# USBSticker01-01.net
KiCad netlist of a schematic drawn in Altium Designer
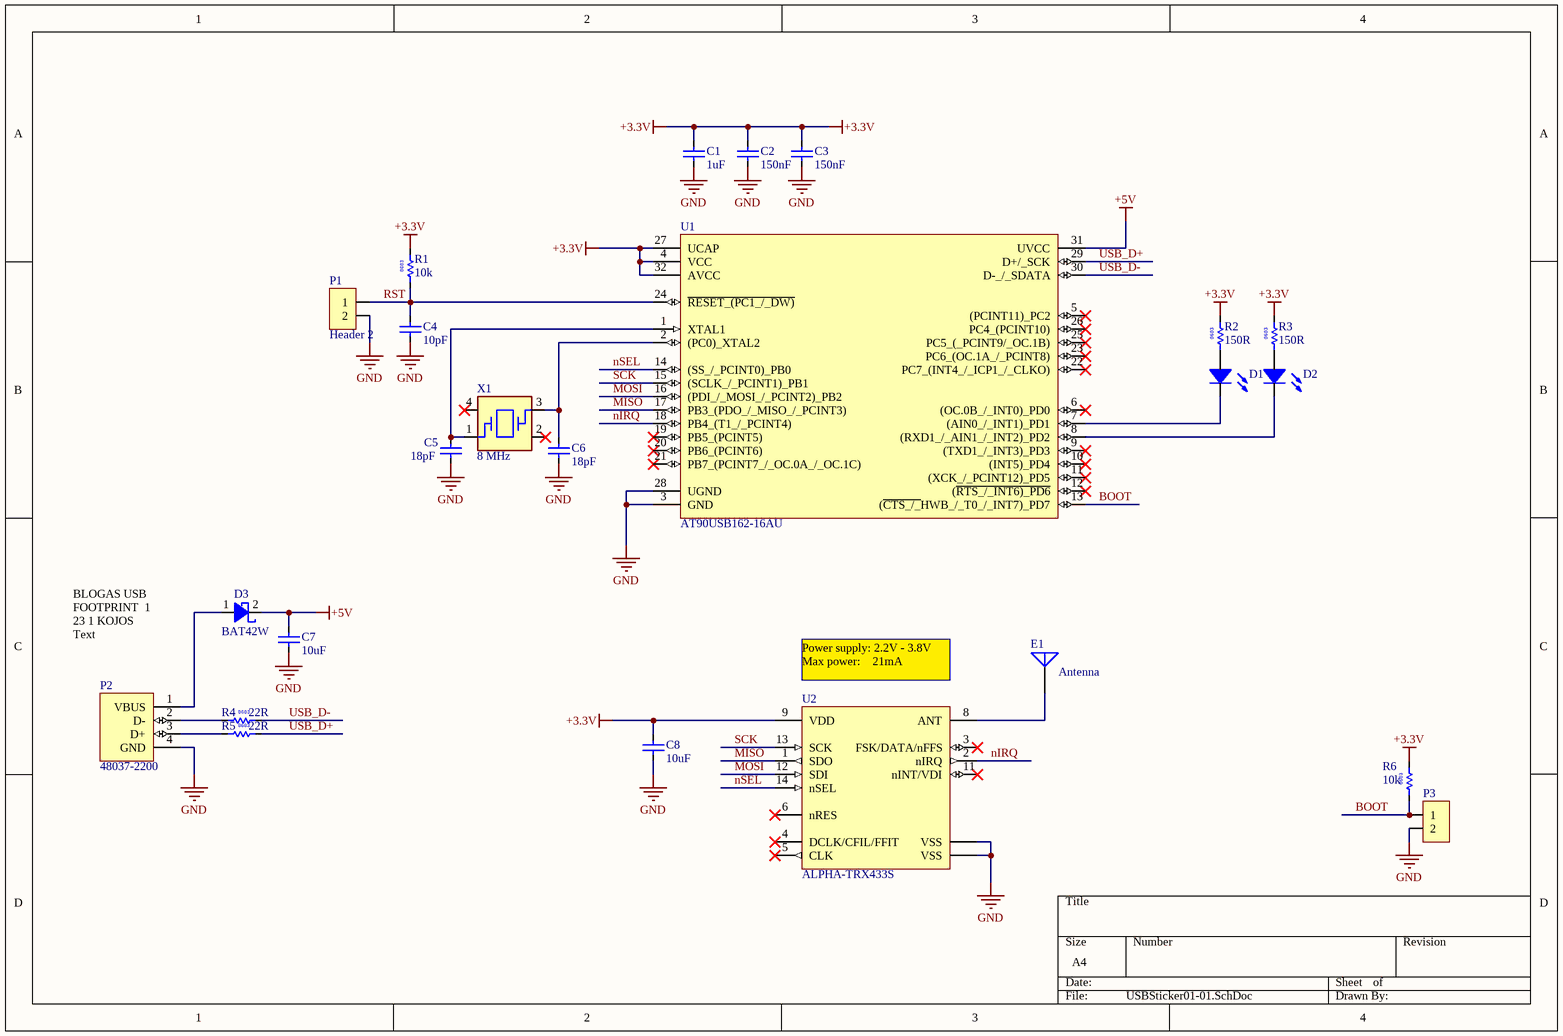
[diagram p0: USBSticker01-01.SchDoc]

(export (version "E")
  (design (tool "Eeschema 10.0.6"))
  (components
    (comp (ref "C1")
      (value "1uF")
      (footprint "CAPC1608N")
      (description "MLCC, 0603, X6S, 25V, 1uF")
      (fields (field (name "PART NUMBER") "C0000022") (field (name "VOLTAGE") "25"))
      (libsource (lib "KTU_DB") (part "C_SM"))
    )
    (comp (ref "C2")
      (value "150nF")
      (footprint "CAPC1608N")
      (description "MLCC, 150nF 16V -20+80% Y5V")
      (fields (field (name "PART NUMBER") "C0000001") (field (name "VOLTAGE") "16"))
      (libsource (lib "KTU_DB") (part "C_SM"))
    )
    (comp (ref "C3")
      (value "150nF")
      (footprint "CAPC1608N")
      (description "MLCC, 150nF 16V -20+80% Y5V")
      (fields (field (name "PART NUMBER") "C0000001") (field (name "VOLTAGE") "16"))
      (libsource (lib "KTU_DB") (part "C_SM"))
    )
    (comp (ref "C4")
      (value "10pF")
      (footprint "CAPC1608N")
      (description "MLCC, 0603, NP0, 50V, 10PF")
      (fields (field (name "PART NUMBER") "C0000042") (field (name "VOLTAGE") "100"))
      (libsource (lib "KTU_DB") (part "C_SM"))
    )
    (comp (ref "C5")
      (value "18pF")
      (footprint "CAPC2012N")
      (description "MLCC, 0805, NPO, 50V, 18pF")
      (fields (field (name "PART NUMBER") "C0000048") (field (name "VOLTAGE") "50"))
      (libsource (lib "KTU_DB") (part "C_SM"))
    )
    (comp (ref "C6")
      (value "18pF")
      (footprint "CAPC2012N")
      (description "MLCC, 0805, NPO, 50V, 18pF")
      (fields (field (name "PART NUMBER") "C0000048") (field (name "VOLTAGE") "50"))
      (libsource (lib "KTU_DB") (part "C_SM"))
    )
    (comp (ref "C7")
      (value "10uF")
      (footprint "CAPC3216N")
      (description "MLCC, 10uF 25V -20%, +80% Y5V 1206")
      (fields (field (name "PART NUMBER") "C0000011") (field (name "VOLTAGE") "25"))
      (libsource (lib "KTU_DB") (part "C_SM"))
    )
    (comp (ref "C8")
      (value "10uF")
      (footprint "CAPC3216N")
      (description "MLCC, 10uF 25V -20%, +80% Y5V 1206")
      (fields (field (name "PART NUMBER") "C0000011") (field (name "VOLTAGE") "25"))
      (libsource (lib "KTU_DB") (part "C_SM"))
    )
    (comp (ref "D1")
      (value "KPT-2012QBC-D")
      (footprint "D0805")
      (description "LED, SMD, 0805, BLUE, 100mCd")
      (fields (field (name "PART NUMBER") "D0000005") (field (name "MANUFACTURER") "KINGBRIGHT"))
      (libsource (lib "KTU_DB") (part "LED"))
    )
    (comp (ref "D2")
      (value "KPT-2012QBC-D")
      (footprint "D0805")
      (description "LED, SMD, 0805, BLUE, 100mCd")
      (fields (field (name "PART NUMBER") "D0000005") (field (name "MANUFACTURER") "KINGBRIGHT"))
      (libsource (lib "KTU_DB") (part "LED"))
    )
    (comp (ref "D3")
      (value "BAT42W")
      (footprint "SOD123")
      (description "Diode Schottkey, 30V, Vf=1V, If=1A, rrt=5ns, SOD123, -55°C to +125°C")
      (fields (field (name "PART NUMBER") "D0000003") (field (name "MANUFACTURER") "VISHAY SEMICONDUCTOR"))
      (libsource (lib "KTU_DB") (part "Diode_SCHOTTKY"))
    )
    (comp (ref "E1")
      (value "Antenna")
      (description "Generic Antenna")
      (fields (field (name "PUBLISHER") "Altium Limited"))
      (libsource (lib "Miscellaneous Devices") (part "Antenna"))
    )
    (comp (ref "P1")
      (value "Header 2")
      (footprint "HDR1X2")
      (description "Header, 2-Pin")
      (fields (field (name "PUBLISHER") "Altium Limited"))
      (libsource (lib "") (part "Header 2_1"))
    )
    (comp (ref "P2")
      (value "48037-2200")
      (footprint "MOLEX 48037-2200")
      (description "SOCKET, USB, PCB, R/A, TYPE A")
      (fields (field (name "MANUFACTURER") "MOLEX"))
      (libsource (lib "UserSchlib") (part "48037-2200"))
    )
    (comp (ref "P3")
      (value "Header 2")
      (footprint "HDR1X2")
      (description "Header, 2-Pin")
      (fields (field (name "PUBLISHER") "Altium Limited"))
      (libsource (lib "UserSchlib") (part "Header 2"))
    )
    (comp (ref "R1")
      (value "10k")
      (footprint "RESC1608N")
      (description "Res, 10K 0.063W 75V 1%  0603")
      (fields (field (name "TOLERANCE") "±1%") (field (name "POWER") "0.063W"))
      (libsource (lib "KTU_DB") (part "R0603"))
    )
    (comp (ref "R2")
      (value "150R")
      (footprint "RESC1608N")
      (description "150R 5% 0603 1/10W")
      (fields (field (name "TOLERANCE") "±5%") (field (name "POWER") "1/10W"))
      (libsource (lib "KTU_DB") (part "R0603"))
    )
    (comp (ref "R3")
      (value "150R")
      (footprint "RESC1608N")
      (description "150R 5% 0603 1/10W")
      (fields (field (name "TOLERANCE") "±5%") (field (name "POWER") "1/10W"))
      (libsource (lib "KTU_DB") (part "R0603"))
    )
    (comp (ref "R4")
      (value "22R")
      (footprint "RESC1608X50N")
      (description "Res, 22R, 0603 (1608 metric), ±1%, 100mW, 75V")
      (libsource (lib "KTU_DB") (part "R0603"))
    )
    (comp (ref "R5")
      (value "22R")
      (footprint "RESC1608X50N")
      (description "Res, 22R, 0603 (1608 metric), ±1%, 100mW, 75V")
      (libsource (lib "KTU_DB") (part "R0603"))
    )
    (comp (ref "R6")
      (value "10k")
      (footprint "RESC1608N")
      (description "Res, 10K 0.063W 75V 1%  0603")
      (fields (field (name "TOLERANCE") "±1%") (field (name "POWER") "0.063W"))
      (libsource (lib "KTU_DB") (part "R0603"))
    )
    (comp (ref "U1")
      (value "AT90USB162-16AU")
      (footprint "QFP80P900X900X120-32N")
      (fields (field (name "MANUFACTURER") "Atmel"))
      (libsource (lib "UserSchlib") (part "AT90USB162-16AU"))
    )
    (comp (ref "U2")
      (value "ALPHA-TRX433S")
      (footprint "ALPHA-TRX")
      (description "RF SOLUTIONS  ALPHA-TRX433S  RF MODULE, TRANSCEIVER, FSK, 433MHZ")
      (fields (field (name "MANUFACTURER") "RF SOLUTIONS"))
      (libsource (lib "UserSchlib") (part "ALPHA-TRX433S"))
    )
    (comp (ref "X1")
      (value "8 MHz")
      (footprint "2SMX-3SMXB")
      (description "CRYSTAL, 8M, 18PF CL, 6X3.6MM SMT")
      (fields (field (name "PART NUMBER") "M0000014") (field (name "TOLERANCE") "± 20ppm"))
      (libsource (lib "KTU_DB") (part "XTAL2"))
    )
  )
  (nets
    (net (code "1") (name "+3.3V") (class "Default")
      (node (ref "C1") (pin "2") (pinfunction "2_2") (pintype "passive"))
      (node (ref "C2") (pin "2") (pinfunction "2_2") (pintype "passive"))
      (node (ref "C3") (pin "2") (pinfunction "2_2") (pintype "passive"))
      (node (ref "C8") (pin "2") (pinfunction "2_2") (pintype "passive"))
      (node (ref "R1") (pin "2") (pinfunction "2_2") (pintype "passive"))
      (node (ref "R2") (pin "2") (pinfunction "2_2") (pintype "passive"))
      (node (ref "R3") (pin "2") (pinfunction "2_2") (pintype "passive"))
      (node (ref "R6") (pin "2") (pinfunction "2_2") (pintype "passive"))
      (node (ref "U1") (pin "27") (pinfunction "UCAP_27") (pintype "power_in"))
      (node (ref "U1") (pin "32") (pinfunction "AVCC_32") (pintype "power_in"))
      (node (ref "U1") (pin "4") (pinfunction "VCC_4") (pintype "power_in"))
      (node (ref "U2") (pin "9") (pinfunction "VDD_9") (pintype "power_in"))
    )
    (net (code "2") (name "+5V") (class "Default")
      (node (ref "C7") (pin "2") (pinfunction "2_2") (pintype "passive"))
      (node (ref "D3") (pin "2") (pinfunction "CATHODE_2") (pintype "passive"))
      (node (ref "U1") (pin "31") (pinfunction "UVCC_31") (pintype "power_in"))
    )
    (net (code "3") (name "/BOOT") (class "Default")
      (node (ref "P3") (pin "1") (pinfunction "1_1") (pintype "passive"))
      (node (ref "R6") (pin "1") (pinfunction "1_1") (pintype "passive"))
      (node (ref "U1") (pin "13") (pinfunction "(~{CTS_/_}HWB_/_T0_/_INT7)_PD7_13") (pintype "bidirectional"))
    )
    (net (code "4") (name "/MISO") (class "Default")
      (node (ref "U1") (pin "17") (pinfunction "PB3_(PDO_/_MISO_/_PCINT3)_17") (pintype "bidirectional"))
      (node (ref "U2") (pin "1") (pinfunction "SDO_1") (pintype "output"))
    )
    (net (code "5") (name "/MOSI") (class "Default")
      (node (ref "U1") (pin "16") (pinfunction "(PDI_/_MOSI_/_PCINT2)_PB2_16") (pintype "bidirectional"))
      (node (ref "U2") (pin "12") (pinfunction "SDI_12") (pintype "input"))
    )
    (net (code "6") (name "/RST") (class "Default")
      (node (ref "C4") (pin "2") (pinfunction "2_2") (pintype "passive"))
      (node (ref "P1") (pin "1") (pinfunction "1_1") (pintype "passive"))
      (node (ref "R1") (pin "1") (pinfunction "1_1") (pintype "passive"))
      (node (ref "U1") (pin "24") (pinfunction "~{RESET_(PC1_/_DW)}_24") (pintype "bidirectional"))
    )
    (net (code "7") (name "/SCK") (class "Default")
      (node (ref "U1") (pin "15") (pinfunction "(SCLK_/_PCINT1)_PB1_15") (pintype "bidirectional"))
      (node (ref "U2") (pin "13") (pinfunction "SCK_13") (pintype "input"))
    )
    (net (code "8") (name "/USB_D+") (class "Default")
      (node (ref "R5") (pin "2") (pinfunction "2_2") (pintype "passive"))
      (node (ref "U1") (pin "29") (pinfunction "D+/_SCK_29") (pintype "bidirectional"))
    )
    (net (code "9") (name "/USB_D-") (class "Default")
      (node (ref "R4") (pin "2") (pinfunction "2_2") (pintype "passive"))
      (node (ref "U1") (pin "30") (pinfunction "D-_/_SDATA_30") (pintype "bidirectional"))
    )
    (net (code "10") (name "/nIRQ") (class "Default")
      (node (ref "U1") (pin "18") (pinfunction "PB4_(T1_/_PCINT4)_18") (pintype "bidirectional"))
      (node (ref "U2") (pin "2") (pinfunction "nIRQ_2") (pintype "output"))
    )
    (net (code "11") (name "/nSEL") (class "Default")
      (node (ref "U1") (pin "14") (pinfunction "(SS_/_PCINT0)_PB0_14") (pintype "bidirectional"))
      (node (ref "U2") (pin "14") (pinfunction "nSEL_14") (pintype "input"))
    )
    (net (code "12") (name "GND") (class "Default")
      (node (ref "C1") (pin "1") (pinfunction "1_1") (pintype "passive"))
      (node (ref "C2") (pin "1") (pinfunction "1_1") (pintype "passive"))
      (node (ref "C3") (pin "1") (pinfunction "1_1") (pintype "passive"))
      (node (ref "C4") (pin "1") (pinfunction "1_1") (pintype "passive"))
      (node (ref "C5") (pin "1") (pinfunction "1_1") (pintype "passive"))
      (node (ref "C6") (pin "1") (pinfunction "1_1") (pintype "passive"))
      (node (ref "C7") (pin "1") (pinfunction "1_1") (pintype "passive"))
      (node (ref "C8") (pin "1") (pinfunction "1_1") (pintype "passive"))
      (node (ref "P1") (pin "2") (pinfunction "2_2") (pintype "passive"))
      (node (ref "P2") (pin "4") (pinfunction "GND_4") (pintype "power_in"))
      (node (ref "P3") (pin "2") (pinfunction "2_2") (pintype "passive"))
      (node (ref "U1") (pin "28") (pinfunction "UGND_28") (pintype "passive"))
      (node (ref "U1") (pin "3") (pinfunction "GND_3") (pintype "passive"))
      (node (ref "U2") (pin "10") (pinfunction "VSS_10") (pintype "power_in"))
      (node (ref "U2") (pin "7") (pinfunction "VSS_7") (pintype "power_in"))
    )
    (net (code "13") (name "Net-(D1-Pad1)") (class "Default")
      (node (ref "D1") (pin "1") (pinfunction "1_1") (pintype "passive"))
      (node (ref "R2") (pin "1") (pinfunction "1_1") (pintype "passive"))
    )
    (net (code "14") (name "Net-(D2-Pad1)") (class "Default")
      (node (ref "D2") (pin "1") (pinfunction "1_1") (pintype "passive"))
      (node (ref "R3") (pin "1") (pinfunction "1_1") (pintype "passive"))
    )
    (net (code "15") (name "Net-(D3-ANODE)") (class "Default")
      (node (ref "D3") (pin "1") (pinfunction "ANODE_1") (pintype "passive"))
      (node (ref "P2") (pin "1") (pinfunction "VBUS_1") (pintype "power_in"))
    )
    (net (code "16") (name "Net-(E1-A)") (class "Default")
      (node (ref "E1") (pin "1") (pinfunction "A_1") (pintype "passive"))
      (node (ref "U2") (pin "8") (pinfunction "ANT_8") (pintype "passive"))
    )
    (net (code "17") (name "Net-(P2-D+)") (class "Default")
      (node (ref "P2") (pin "3") (pinfunction "D+_3") (pintype "bidirectional"))
      (node (ref "R5") (pin "1") (pinfunction "1_1") (pintype "passive"))
    )
    (net (code "18") (name "Net-(P2-D-)") (class "Default")
      (node (ref "P2") (pin "2") (pinfunction "D-_2") (pintype "bidirectional"))
      (node (ref "R4") (pin "1") (pinfunction "1_1") (pintype "passive"))
    )
    (net (code "19") (name "Net-(U1-(AIN0_{slash}_INT1)_PD1)") (class "Default")
      (node (ref "D1") (pin "2") (pinfunction "2_2") (pintype "passive"))
      (node (ref "U1") (pin "7") (pinfunction "(AIN0_/_INT1)_PD1_7") (pintype "bidirectional"))
    )
    (net (code "20") (name "Net-(U1-(PC0)_XTAL2)") (class "Default")
      (node (ref "C6") (pin "2") (pinfunction "2_2") (pintype "passive"))
      (node (ref "U1") (pin "2") (pinfunction "(PC0)_XTAL2_2") (pintype "bidirectional"))
      (node (ref "X1") (pin "3") (pinfunction "3_3") (pintype "passive"))
    )
    (net (code "21") (name "Net-(U1-(RXD1_{slash}_AIN1_{slash}_INT2)_PD2)") (class "Default")
      (node (ref "D2") (pin "2") (pinfunction "2_2") (pintype "passive"))
      (node (ref "U1") (pin "8") (pinfunction "(RXD1_/_AIN1_/_INT2)_PD2_8") (pintype "bidirectional"))
    )
    (net (code "22") (name "Net-(U1-XTAL1)") (class "Default")
      (node (ref "C5") (pin "2") (pinfunction "2_2") (pintype "passive"))
      (node (ref "U1") (pin "1") (pinfunction "XTAL1_1") (pintype "input"))
      (node (ref "X1") (pin "1") (pinfunction "1_1") (pintype "passive"))
    )
    (net (code "23") (name "unconnected-(U1-(INT5)_PD4-Pad10)") (class "Default")
      (node (ref "U1") (pin "10") (pinfunction "(INT5)_PD4_10") (pintype "bidirectional+no_connect"))
    )
    (net (code "24") (name "unconnected-(U1-(OC.0B_{slash}_INT0)_PD0-Pad6)") (class "Default")
      (node (ref "U1") (pin "6") (pinfunction "(OC.0B_/_INT0)_PD0_6") (pintype "bidirectional+no_connect"))
    )
    (net (code "25") (name "unconnected-(U1-(PCINT11)_PC2-Pad5)") (class "Default")
      (node (ref "U1") (pin "5") (pinfunction "(PCINT11)_PC2_5") (pintype "bidirectional+no_connect"))
    )
    (net (code "26") (name "unconnected-(U1-(TXD1_{slash}_INT3)_PD3-Pad9)") (class "Default")
      (node (ref "U1") (pin "9") (pinfunction "(TXD1_/_INT3)_PD3_9") (pintype "bidirectional+no_connect"))
    )
    (net (code "27") (name "unconnected-(U1-(XCK_{slash}_PCINT12)_PD5-Pad11)") (class "Default")
      (node (ref "U1") (pin "11") (pinfunction "(XCK_/_PCINT12)_PD5_11") (pintype "bidirectional+no_connect"))
    )
    (net (code "28") (name "unconnected-(U1-(~{RTS_{slash}_INT6)_PD6}-Pad12)") (class "Default")
      (node (ref "U1") (pin "12") (pinfunction "(~{RTS_/_INT6)_PD6}_12") (pintype "bidirectional+no_connect"))
    )
    (net (code "29") (name "unconnected-(U1-PB5_(PCINT5)-Pad19)") (class "Default")
      (node (ref "U1") (pin "19") (pinfunction "PB5_(PCINT5)_19") (pintype "bidirectional+no_connect"))
    )
    (net (code "30") (name "unconnected-(U1-PB6_(PCINT6)-Pad20)") (class "Default")
      (node (ref "U1") (pin "20") (pinfunction "PB6_(PCINT6)_20") (pintype "bidirectional+no_connect"))
    )
    (net (code "31") (name "unconnected-(U1-PB7_(PCINT7_{slash}_OC.0A_{slash}_OC.1C)-Pad21)") (class "Default")
      (node (ref "U1") (pin "21") (pinfunction "PB7_(PCINT7_/_OC.0A_/_OC.1C)_21") (pintype "bidirectional+no_connect"))
    )
    (net (code "32") (name "unconnected-(U1-PC4_(PCINT10)-Pad26)") (class "Default")
      (node (ref "U1") (pin "26") (pinfunction "PC4_(PCINT10)_26") (pintype "bidirectional+no_connect"))
    )
    (net (code "33") (name "unconnected-(U1-PC5_(_PCINT9{slash}_OC.1B)-Pad25)") (class "Default")
      (node (ref "U1") (pin "25") (pinfunction "PC5_(_PCINT9/_OC.1B)_25") (pintype "bidirectional+no_connect"))
    )
    (net (code "34") (name "unconnected-(U1-PC6_(OC.1A_{slash}_PCINT8)-Pad23)") (class "Default")
      (node (ref "U1") (pin "23") (pinfunction "PC6_(OC.1A_/_PCINT8)_23") (pintype "bidirectional+no_connect"))
    )
    (net (code "35") (name "unconnected-(U1-PC7_(INT4_{slash}_ICP1_{slash}_CLKO)-Pad22)") (class "Default")
      (node (ref "U1") (pin "22") (pinfunction "PC7_(INT4_/_ICP1_/_CLKO)_22") (pintype "bidirectional+no_connect"))
    )
    (net (code "36") (name "unconnected-(U2-CLK-Pad5)") (class "Default")
      (node (ref "U2") (pin "5") (pinfunction "CLK_5") (pintype "output+no_connect"))
    )
    (net (code "37") (name "unconnected-(U2-DCLK{slash}CFIL{slash}FFIT-Pad4)") (class "Default")
      (node (ref "U2") (pin "4") (pinfunction "DCLK/CFIL/FFIT_4") (pintype "passive+no_connect"))
    )
    (net (code "38") (name "unconnected-(U2-FSK{slash}DATA{slash}nFFS-Pad3)") (class "Default")
      (node (ref "U2") (pin "3") (pinfunction "FSK/DATA/nFFS_3") (pintype "bidirectional+no_connect"))
    )
    (net (code "39") (name "unconnected-(U2-nINT{slash}VDI-Pad11)") (class "Default")
      (node (ref "U2") (pin "11") (pinfunction "nINT/VDI_11") (pintype "bidirectional+no_connect"))
    )
    (net (code "40") (name "unconnected-(U2-nRES-Pad6)") (class "Default")
      (node (ref "U2") (pin "6") (pinfunction "nRES_6") (pintype "passive+no_connect"))
    )
    (net (code "41") (name "unconnected-(X1-Pad2)") (class "Default")
      (node (ref "X1") (pin "2") (pinfunction "2_2") (pintype "passive+no_connect"))
    )
    (net (code "42") (name "unconnected-(X1-Pad4)") (class "Default")
      (node (ref "X1") (pin "4") (pinfunction "4_4") (pintype "passive+no_connect"))
    )
  )
)
